# schematic.net
KiCad netlist of a schematic drawn in Altium Designer
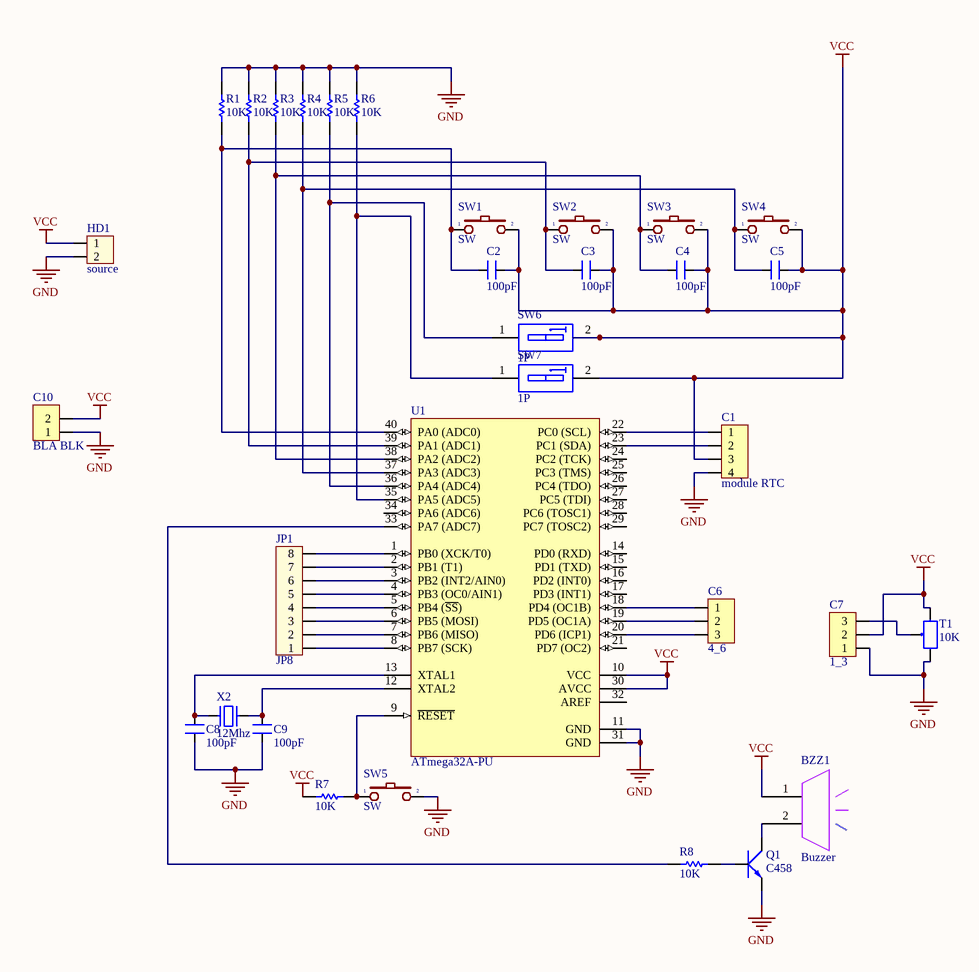
[diagram p0: schematic.SchDoc]

(export (version "E")
  (design (tool "Eeschema 10.0.6"))
  (components
    (comp (ref "BZZ1")
      (value "Buzzer")
      (footprint "buzzer 5V")
      (libsource (lib "my Library") (part "Buzzer"))
    )
    (comp (ref "C1")
      (value "module RTC")
      (footprint "HDR4")
      (description "Header IDC, 4 x 1 Pin Vertical 2.54mm Pitch (Non-Boxed, Male)")
      (fields
        (field (name "MANUFACTURER") "Würth Elektronik eiSos GmbH")
        (field (name "PARTNO") "613002143121")
        (field (name "CREATED BY") "Karrer Zheng")
      )
      (libsource (lib "KhanhBK_SCH_Library_1") (part "Header4"))
    )
    (comp (ref "C2")
      (value "100pF")
      (footprint "CN1")
      (description "Cap np  1pF - 472pF")
      (libsource (lib "syhaunguyen") (part "CN1"))
    )
    (comp (ref "C3")
      (value "100pF")
      (footprint "CN1")
      (description "Cap np  1pF - 472pF")
      (libsource (lib "syhaunguyen") (part "CN1"))
    )
    (comp (ref "C4")
      (value "100pF")
      (footprint "CN1")
      (description "Cap np  1pF - 472pF")
      (libsource (lib "syhaunguyen") (part "CN1"))
    )
    (comp (ref "C5")
      (value "100pF")
      (footprint "CN1")
      (description "Cap np  1pF - 472pF")
      (libsource (lib "syhaunguyen") (part "CN1"))
    )
    (comp (ref "C6")
      (value "4_6")
      (footprint "HDR3")
      (description "Header IDC, 3 x 1 Pin Vertical 2.54mm Pitch (Non-Boxed, Male)")
      (fields
        (field (name "MANUFACTURER") "Würth Elektronik eiSos GmbH")
        (field (name "PARTNO") "613002143121")
        (field (name "CREATED BY") "Karrer Zheng")
      )
      (libsource (lib "") (part "Header3_1"))
    )
    (comp (ref "C7")
      (value "1_3")
      (footprint "HDR3")
      (description "Header IDC, 3 x 1 Pin Vertical 2.54mm Pitch (Non-Boxed, Male)")
      (fields
        (field (name "MANUFACTURER") "Würth Elektronik eiSos GmbH")
        (field (name "PARTNO") "613002143121")
        (field (name "CREATED BY") "Karrer Zheng")
      )
      (libsource (lib "KhanhBK_SCH_Library_1") (part "Header3"))
    )
    (comp (ref "C8")
      (value "100pF")
      (footprint "CN1")
      (description "Cap np  1pF - 472pF")
      (libsource (lib "syhaunguyen") (part "CN1"))
    )
    (comp (ref "C9")
      (value "100pF")
      (footprint "CN1")
      (description "Cap np  1pF - 472pF")
      (libsource (lib "syhaunguyen") (part "CN1"))
    )
    (comp (ref "C10")
      (value "BLA BLK")
      (footprint "HDR2")
      (description "Header IDC, 2 x 1 Pin Vertical 2.54mm Pitch (Non-Boxed, Male)")
      (fields
        (field (name "MANUFACTURER") "Würth Elektronik eiSos GmbH")
        (field (name "PARTNO") "613002143121")
        (field (name "CREATED BY") "Karrer Zheng")
      )
      (libsource (lib "KhanhBK_SCH_Library_1") (part "Header2"))
    )
    (comp (ref "HD1")
      (value "source")
      (footprint "HED2")
      (description "Header 2 (Green)")
      (libsource (lib "my Library") (part "Header 2"))
    )
    (comp (ref "JP1")
      (value "JP8")
      (footprint "Header8")
      (description "Connector 8")
      (libsource (lib "KhanhBK_SCH_Library_1") (part "Header8"))
    )
    (comp (ref "Q1")
      (value "C458")
      (footprint "TO92-123")
      (description "NPN 600mW, ECB")
      (libsource (lib "KhanhBK_SCH_Library_1") (part "C458"))
    )
    (comp (ref "R1")
      (value "10K")
      (footprint "R1/4W")
      (description "Resistor")
      (fields
        (field (name "MANUFACTURER") "Generic Components")
        (field (name "Comment") "Res1")
        (field (name "PUBLISHER") "Altium Hobart Technology Centre")
      )
      (libsource (lib "syhaunguyen") (part "Res1_1"))
    )
    (comp (ref "R2")
      (value "10K")
      (footprint "R1/4W")
      (description "Resistor")
      (fields
        (field (name "MANUFACTURER") "Generic Components")
        (field (name "Comment") "Res1")
        (field (name "PUBLISHER") "Altium Hobart Technology Centre")
      )
      (libsource (lib "syhaunguyen") (part "Res1_1"))
    )
    (comp (ref "R3")
      (value "10K")
      (footprint "R1/4W")
      (description "Resistor")
      (fields
        (field (name "MANUFACTURER") "Generic Components")
        (field (name "Comment") "Res1")
        (field (name "PUBLISHER") "Altium Hobart Technology Centre")
      )
      (libsource (lib "syhaunguyen") (part "Res1_1"))
    )
    (comp (ref "R4")
      (value "10K")
      (footprint "R1/4W")
      (description "Resistor")
      (fields
        (field (name "MANUFACTURER") "Generic Components")
        (field (name "Comment") "Res1")
        (field (name "PUBLISHER") "Altium Hobart Technology Centre")
      )
      (libsource (lib "syhaunguyen") (part "Res1_1"))
    )
    (comp (ref "R5")
      (value "10K")
      (footprint "R1/4W")
      (description "Resistor")
      (fields
        (field (name "MANUFACTURER") "Generic Components")
        (field (name "Comment") "Res1")
        (field (name "PUBLISHER") "Altium Hobart Technology Centre")
      )
      (libsource (lib "syhaunguyen") (part "Res1_1"))
    )
    (comp (ref "R6")
      (value "10K")
      (footprint "R1/4W")
      (description "Resistor")
      (fields
        (field (name "MANUFACTURER") "Generic Components")
        (field (name "Comment") "Res1")
        (field (name "PUBLISHER") "Altium Hobart Technology Centre")
      )
      (libsource (lib "syhaunguyen") (part "Res1_1"))
    )
    (comp (ref "R7")
      (value "10K")
      (footprint "R1/4W")
      (description "Resistor")
      (fields
        (field (name "MANUFACTURER") "Generic Components")
        (field (name "Comment") "Res1")
        (field (name "PUBLISHER") "Altium Hobart Technology Centre")
      )
      (libsource (lib "syhaunguyen") (part "Res1_1"))
    )
    (comp (ref "R8")
      (value "10K")
      (footprint "R1/4W")
      (description "Resistor")
      (fields
        (field (name "MANUFACTURER") "Generic Components")
        (field (name "Comment") "Res1")
        (field (name "PUBLISHER") "Altium Hobart Technology Centre")
      )
      (libsource (lib "syhaunguyen") (part "Res1_1"))
    )
    (comp (ref "SW1")
      (value "SW")
      (footprint "SW2")
      (description "Switch button 2 pin")
      (libsource (lib "syhaunguyen") (part "SW2"))
    )
    (comp (ref "SW2")
      (value "SW")
      (footprint "SW2")
      (description "Switch button 2 pin")
      (libsource (lib "syhaunguyen") (part "SW2"))
    )
    (comp (ref "SW3")
      (value "SW")
      (footprint "SW2")
      (description "Switch button 2 pin")
      (libsource (lib "syhaunguyen") (part "SW2"))
    )
    (comp (ref "SW4")
      (value "SW")
      (footprint "SW2")
      (description "Switch button 2 pin")
      (libsource (lib "syhaunguyen") (part "SW2"))
    )
    (comp (ref "SW5")
      (value "SW")
      (footprint "SW2")
      (description "Switch button 2 pin")
      (libsource (lib "syhaunguyen") (part "SW2"))
    )
    (comp (ref "SW6")
      (value "1P")
      (footprint "SWITCH BIT 1")
      (description "Cắm")
      (libsource (lib "THU VIEN SCH") (part "Cong Tac Bits 1P"))
    )
    (comp (ref "SW7")
      (value "1P")
      (footprint "SWITCH BIT 1")
      (description "Cắm")
      (libsource (lib "THU VIEN SCH") (part "Cong Tac Bits 1P"))
    )
    (comp (ref "T1")
      (value "10K")
      (footprint "RVAR10K")
      (description "Cắm")
      (libsource (lib "THU VIEN SCH") (part "Bien Tro Tinh Chinh 10K"))
    )
    (comp (ref "U1")
      (value "ATmega32A-PU")
      (footprint "DIP40/W0.6")
      (description "8-Bit AVR Microcontroller with 32K Bytes of In-System Programmable Flash Memory")
      (fields (field (name "PUBLISHER") "Altium Limited"))
      (libsource (lib "KhanhBK_SCH_Library_1") (part "ATmega32A-PU"))
    )
    (comp (ref "X2")
      (value "12Mhz")
      (footprint "XT2")
      (description "Crystal, 32.768 KHz, -40 to 85 degC, 3.2 x 1.5 x 0.9 mm SMD")
      (libsource (lib "KhanhBK_SCH_Library_1") (part "XT2"))
    )
  )
  (nets
    (net (code "1") (name "GND") (class "Default")
      (node (ref "C1") (pin "4") (pinfunction "4_4") (pintype "passive"))
      (node (ref "C10") (pin "1") (pinfunction "1_1") (pintype "passive"))
      (node (ref "C7") (pin "1") (pinfunction "1_1") (pintype "passive"))
      (node (ref "C8") (pin "1") (pinfunction "1_1") (pintype "passive"))
      (node (ref "C9") (pin "1") (pinfunction "1_1") (pintype "passive"))
      (node (ref "HD1") (pin "2") (pinfunction "2_2") (pintype "passive"))
      (node (ref "Q1") (pin "1") (pinfunction "E_1") (pintype "passive"))
      (node (ref "R1") (pin "2") (pinfunction "2_2") (pintype "passive"))
      (node (ref "R2") (pin "2") (pinfunction "2_2") (pintype "passive"))
      (node (ref "R3") (pin "2") (pinfunction "2_2") (pintype "passive"))
      (node (ref "R4") (pin "2") (pinfunction "2_2") (pintype "passive"))
      (node (ref "R5") (pin "2") (pinfunction "2_2") (pintype "passive"))
      (node (ref "R6") (pin "2") (pinfunction "2_2") (pintype "passive"))
      (node (ref "SW5") (pin "2") (pinfunction "2_2") (pintype "passive"))
      (node (ref "T1") (pin "1") (pinfunction "1_1") (pintype "passive"))
      (node (ref "U1") (pin "11") (pinfunction "GND_11") (pintype "power_in"))
      (node (ref "U1") (pin "31") (pinfunction "GND_31") (pintype "power_in"))
    )
    (net (code "2") (name "Net-(C7-Pad3)") (class "Default")
      (node (ref "C7") (pin "3") (pinfunction "3_3") (pintype "passive"))
      (node (ref "T1") (pin "2") (pinfunction "2_2") (pintype "passive"))
    )
    (net (code "3") (name "Net-(Q1-B)") (class "Default")
      (node (ref "Q1") (pin "3") (pinfunction "B_3") (pintype "passive"))
      (node (ref "R8") (pin "1") (pinfunction "1_1") (pintype "passive"))
    )
    (net (code "4") (name "Net-(Q1-C)") (class "Default")
      (node (ref "BZZ1") (pin "2") (pinfunction "2_2") (pintype "passive"))
      (node (ref "Q1") (pin "2") (pinfunction "C_2") (pintype "passive"))
    )
    (net (code "5") (name "Net-(SW6-A1)") (class "Default")
      (node (ref "R5") (pin "1") (pinfunction "1_1") (pintype "passive"))
      (node (ref "SW6") (pin "1") (pinfunction "A1_1") (pintype "passive"))
      (node (ref "U1") (pin "36") (pinfunction "PA4_(ADC4)_36") (pintype "bidirectional"))
    )
    (net (code "6") (name "Net-(SW7-A1)") (class "Default")
      (node (ref "R6") (pin "1") (pinfunction "1_1") (pintype "passive"))
      (node (ref "SW7") (pin "1") (pinfunction "A1_1") (pintype "passive"))
      (node (ref "U1") (pin "35") (pinfunction "PA5_(ADC5)_35") (pintype "bidirectional"))
    )
    (net (code "7") (name "Net-(U1-PA0_(ADC0))") (class "Default")
      (node (ref "C2") (pin "1") (pinfunction "1_1") (pintype "passive"))
      (node (ref "R1") (pin "1") (pinfunction "1_1") (pintype "passive"))
      (node (ref "SW1") (pin "1") (pinfunction "1_1") (pintype "passive"))
      (node (ref "U1") (pin "40") (pinfunction "PA0_(ADC0)_40") (pintype "bidirectional"))
    )
    (net (code "8") (name "Net-(U1-PA1_(ADC1))") (class "Default")
      (node (ref "C3") (pin "1") (pinfunction "1_1") (pintype "passive"))
      (node (ref "R2") (pin "1") (pinfunction "1_1") (pintype "passive"))
      (node (ref "SW2") (pin "1") (pinfunction "1_1") (pintype "passive"))
      (node (ref "U1") (pin "39") (pinfunction "PA1_(ADC1)_39") (pintype "bidirectional"))
    )
    (net (code "9") (name "Net-(U1-PA2_(ADC2))") (class "Default")
      (node (ref "C4") (pin "1") (pinfunction "1_1") (pintype "passive"))
      (node (ref "R3") (pin "1") (pinfunction "1_1") (pintype "passive"))
      (node (ref "SW3") (pin "1") (pinfunction "1_1") (pintype "passive"))
      (node (ref "U1") (pin "38") (pinfunction "PA2_(ADC2)_38") (pintype "bidirectional"))
    )
    (net (code "10") (name "Net-(U1-PA3_(ADC3))") (class "Default")
      (node (ref "C5") (pin "1") (pinfunction "1_1") (pintype "passive"))
      (node (ref "R4") (pin "1") (pinfunction "1_1") (pintype "passive"))
      (node (ref "SW4") (pin "1") (pinfunction "1_1") (pintype "passive"))
      (node (ref "U1") (pin "37") (pinfunction "PA3_(ADC3)_37") (pintype "bidirectional"))
    )
    (net (code "11") (name "Net-(U1-PA7_(ADC7))") (class "Default")
      (node (ref "R8") (pin "2") (pinfunction "2_2") (pintype "passive"))
      (node (ref "U1") (pin "33") (pinfunction "PA7_(ADC7)_33") (pintype "bidirectional"))
    )
    (net (code "12") (name "Net-(U1-PB0_(XCK{slash}T0))") (class "Default")
      (node (ref "JP1") (pin "8") (pinfunction "8_8") (pintype "passive"))
      (node (ref "U1") (pin "1") (pinfunction "PB0_(XCK/T0)_1") (pintype "bidirectional"))
    )
    (net (code "13") (name "Net-(U1-PB1_(T1))") (class "Default")
      (node (ref "JP1") (pin "7") (pinfunction "7_7") (pintype "passive"))
      (node (ref "U1") (pin "2") (pinfunction "PB1_(T1)_2") (pintype "bidirectional"))
    )
    (net (code "14") (name "Net-(U1-PB2_(INT2{slash}AIN0))") (class "Default")
      (node (ref "JP1") (pin "6") (pinfunction "6_6") (pintype "passive"))
      (node (ref "U1") (pin "3") (pinfunction "PB2_(INT2/AIN0)_3") (pintype "bidirectional"))
    )
    (net (code "15") (name "Net-(U1-PB3_(OC0{slash}AIN1))") (class "Default")
      (node (ref "JP1") (pin "5") (pinfunction "5_5") (pintype "passive"))
      (node (ref "U1") (pin "4") (pinfunction "PB3_(OC0/AIN1)_4") (pintype "bidirectional"))
    )
    (net (code "16") (name "Net-(U1-PB4_(~{SS}))") (class "Default")
      (node (ref "JP1") (pin "4") (pinfunction "4_4") (pintype "passive"))
      (node (ref "U1") (pin "5") (pinfunction "PB4_(~{SS})_5") (pintype "bidirectional"))
    )
    (net (code "17") (name "Net-(U1-PB5_(MOSI))") (class "Default")
      (node (ref "JP1") (pin "3") (pinfunction "3_3") (pintype "passive"))
      (node (ref "U1") (pin "6") (pinfunction "PB5_(MOSI)_6") (pintype "bidirectional"))
    )
    (net (code "18") (name "Net-(U1-PB6_(MISO))") (class "Default")
      (node (ref "JP1") (pin "2") (pinfunction "2_2") (pintype "passive"))
      (node (ref "U1") (pin "7") (pinfunction "PB6_(MISO)_7") (pintype "bidirectional"))
    )
    (net (code "19") (name "Net-(U1-PB7_(SCK))") (class "Default")
      (node (ref "JP1") (pin "1") (pinfunction "1_1") (pintype "passive"))
      (node (ref "U1") (pin "8") (pinfunction "PB7_(SCK)_8") (pintype "bidirectional"))
    )
    (net (code "20") (name "Net-(U1-PC0_(SCL))") (class "Default")
      (node (ref "C1") (pin "1") (pinfunction "1_1") (pintype "passive"))
      (node (ref "U1") (pin "22") (pinfunction "PC0_(SCL)_22") (pintype "bidirectional"))
    )
    (net (code "21") (name "Net-(U1-PC1_(SDA))") (class "Default")
      (node (ref "C1") (pin "2") (pinfunction "2_2") (pintype "passive"))
      (node (ref "U1") (pin "23") (pinfunction "PC1_(SDA)_23") (pintype "bidirectional"))
    )
    (net (code "22") (name "Net-(U1-PD4_(OC1B))") (class "Default")
      (node (ref "C6") (pin "1") (pinfunction "1_1") (pintype "passive"))
      (node (ref "U1") (pin "18") (pinfunction "PD4_(OC1B)_18") (pintype "bidirectional"))
    )
    (net (code "23") (name "Net-(U1-PD5_(OC1A))") (class "Default")
      (node (ref "C6") (pin "2") (pinfunction "2_2") (pintype "passive"))
      (node (ref "U1") (pin "19") (pinfunction "PD5_(OC1A)_19") (pintype "bidirectional"))
    )
    (net (code "24") (name "Net-(U1-PD6_(ICP1))") (class "Default")
      (node (ref "C6") (pin "3") (pinfunction "3_3") (pintype "passive"))
      (node (ref "U1") (pin "20") (pinfunction "PD6_(ICP1)_20") (pintype "bidirectional"))
    )
    (net (code "25") (name "Net-(U1-XTAL1)") (class "Default")
      (node (ref "C8") (pin "2") (pinfunction "2_2") (pintype "passive"))
      (node (ref "U1") (pin "13") (pinfunction "XTAL1_13") (pintype "passive"))
      (node (ref "X2") (pin "1") (pinfunction "1_1") (pintype "passive"))
    )
    (net (code "26") (name "Net-(U1-XTAL2)") (class "Default")
      (node (ref "C9") (pin "2") (pinfunction "2_2") (pintype "passive"))
      (node (ref "U1") (pin "12") (pinfunction "XTAL2_12") (pintype "passive"))
      (node (ref "X2") (pin "2") (pinfunction "2_2") (pintype "passive"))
    )
    (net (code "27") (name "Net-(U1-~{RESET})") (class "Default")
      (node (ref "R7") (pin "1") (pinfunction "1_1") (pintype "passive"))
      (node (ref "SW5") (pin "1") (pinfunction "1_1") (pintype "passive"))
      (node (ref "U1") (pin "9") (pinfunction "~{RESET}_9") (pintype "input"))
    )
    (net (code "28") (name "VCC") (class "Default")
      (node (ref "BZZ1") (pin "1") (pinfunction "1_1") (pintype "passive"))
      (node (ref "C1") (pin "3") (pinfunction "3_3") (pintype "passive"))
      (node (ref "C10") (pin "2") (pinfunction "2_2") (pintype "passive"))
      (node (ref "C2") (pin "2") (pinfunction "2_2") (pintype "passive"))
      (node (ref "C3") (pin "2") (pinfunction "2_2") (pintype "passive"))
      (node (ref "C4") (pin "2") (pinfunction "2_2") (pintype "passive"))
      (node (ref "C5") (pin "2") (pinfunction "2_2") (pintype "passive"))
      (node (ref "C7") (pin "2") (pinfunction "2_2") (pintype "passive"))
      (node (ref "HD1") (pin "1") (pinfunction "1_1") (pintype "passive"))
      (node (ref "R7") (pin "2") (pinfunction "2_2") (pintype "passive"))
      (node (ref "SW1") (pin "2") (pinfunction "2_2") (pintype "passive"))
      (node (ref "SW2") (pin "2") (pinfunction "2_2") (pintype "passive"))
      (node (ref "SW3") (pin "2") (pinfunction "2_2") (pintype "passive"))
      (node (ref "SW4") (pin "2") (pinfunction "2_2") (pintype "passive"))
      (node (ref "SW6") (pin "2") (pinfunction "B1_2") (pintype "passive"))
      (node (ref "SW7") (pin "2") (pinfunction "B1_2") (pintype "passive"))
      (node (ref "T1") (pin "3") (pinfunction "3_3") (pintype "passive"))
      (node (ref "U1") (pin "10") (pinfunction "VCC_10") (pintype "power_in"))
      (node (ref "U1") (pin "30") (pinfunction "AVCC_30") (pintype "power_in"))
    )
    (net (code "29") (name "unconnected-(U1-AREF-Pad32)") (class "Default")
      (node (ref "U1") (pin "32") (pinfunction "AREF_32") (pintype "power_in"))
    )
    (net (code "30") (name "unconnected-(U1-PA6_(ADC6)-Pad34)") (class "Default")
      (node (ref "U1") (pin "34") (pinfunction "PA6_(ADC6)_34") (pintype "bidirectional"))
    )
    (net (code "31") (name "unconnected-(U1-PC2_(TCK)-Pad24)") (class "Default")
      (node (ref "U1") (pin "24") (pinfunction "PC2_(TCK)_24") (pintype "bidirectional"))
    )
    (net (code "32") (name "unconnected-(U1-PC3_(TMS)-Pad25)") (class "Default")
      (node (ref "U1") (pin "25") (pinfunction "PC3_(TMS)_25") (pintype "bidirectional"))
    )
    (net (code "33") (name "unconnected-(U1-PC4_(TDO)-Pad26)") (class "Default")
      (node (ref "U1") (pin "26") (pinfunction "PC4_(TDO)_26") (pintype "bidirectional"))
    )
    (net (code "34") (name "unconnected-(U1-PC5_(TDI)-Pad27)") (class "Default")
      (node (ref "U1") (pin "27") (pinfunction "PC5_(TDI)_27") (pintype "bidirectional"))
    )
    (net (code "35") (name "unconnected-(U1-PC6_(TOSC1)-Pad28)") (class "Default")
      (node (ref "U1") (pin "28") (pinfunction "PC6_(TOSC1)_28") (pintype "bidirectional"))
    )
    (net (code "36") (name "unconnected-(U1-PC7_(TOSC2)-Pad29)") (class "Default")
      (node (ref "U1") (pin "29") (pinfunction "PC7_(TOSC2)_29") (pintype "bidirectional"))
    )
    (net (code "37") (name "unconnected-(U1-PD0_(RXD)-Pad14)") (class "Default")
      (node (ref "U1") (pin "14") (pinfunction "PD0_(RXD)_14") (pintype "bidirectional"))
    )
    (net (code "38") (name "unconnected-(U1-PD1_(TXD)-Pad15)") (class "Default")
      (node (ref "U1") (pin "15") (pinfunction "PD1_(TXD)_15") (pintype "bidirectional"))
    )
    (net (code "39") (name "unconnected-(U1-PD2_(INT0)-Pad16)") (class "Default")
      (node (ref "U1") (pin "16") (pinfunction "PD2_(INT0)_16") (pintype "bidirectional"))
    )
    (net (code "40") (name "unconnected-(U1-PD3_(INT1)-Pad17)") (class "Default")
      (node (ref "U1") (pin "17") (pinfunction "PD3_(INT1)_17") (pintype "bidirectional"))
    )
    (net (code "41") (name "unconnected-(U1-PD7_(OC2)-Pad21)") (class "Default")
      (node (ref "U1") (pin "21") (pinfunction "PD7_(OC2)_21") (pintype "bidirectional"))
    )
  )
)
